# 20190520508.net
KiCad netlist of a schematic drawn in Altium Designer
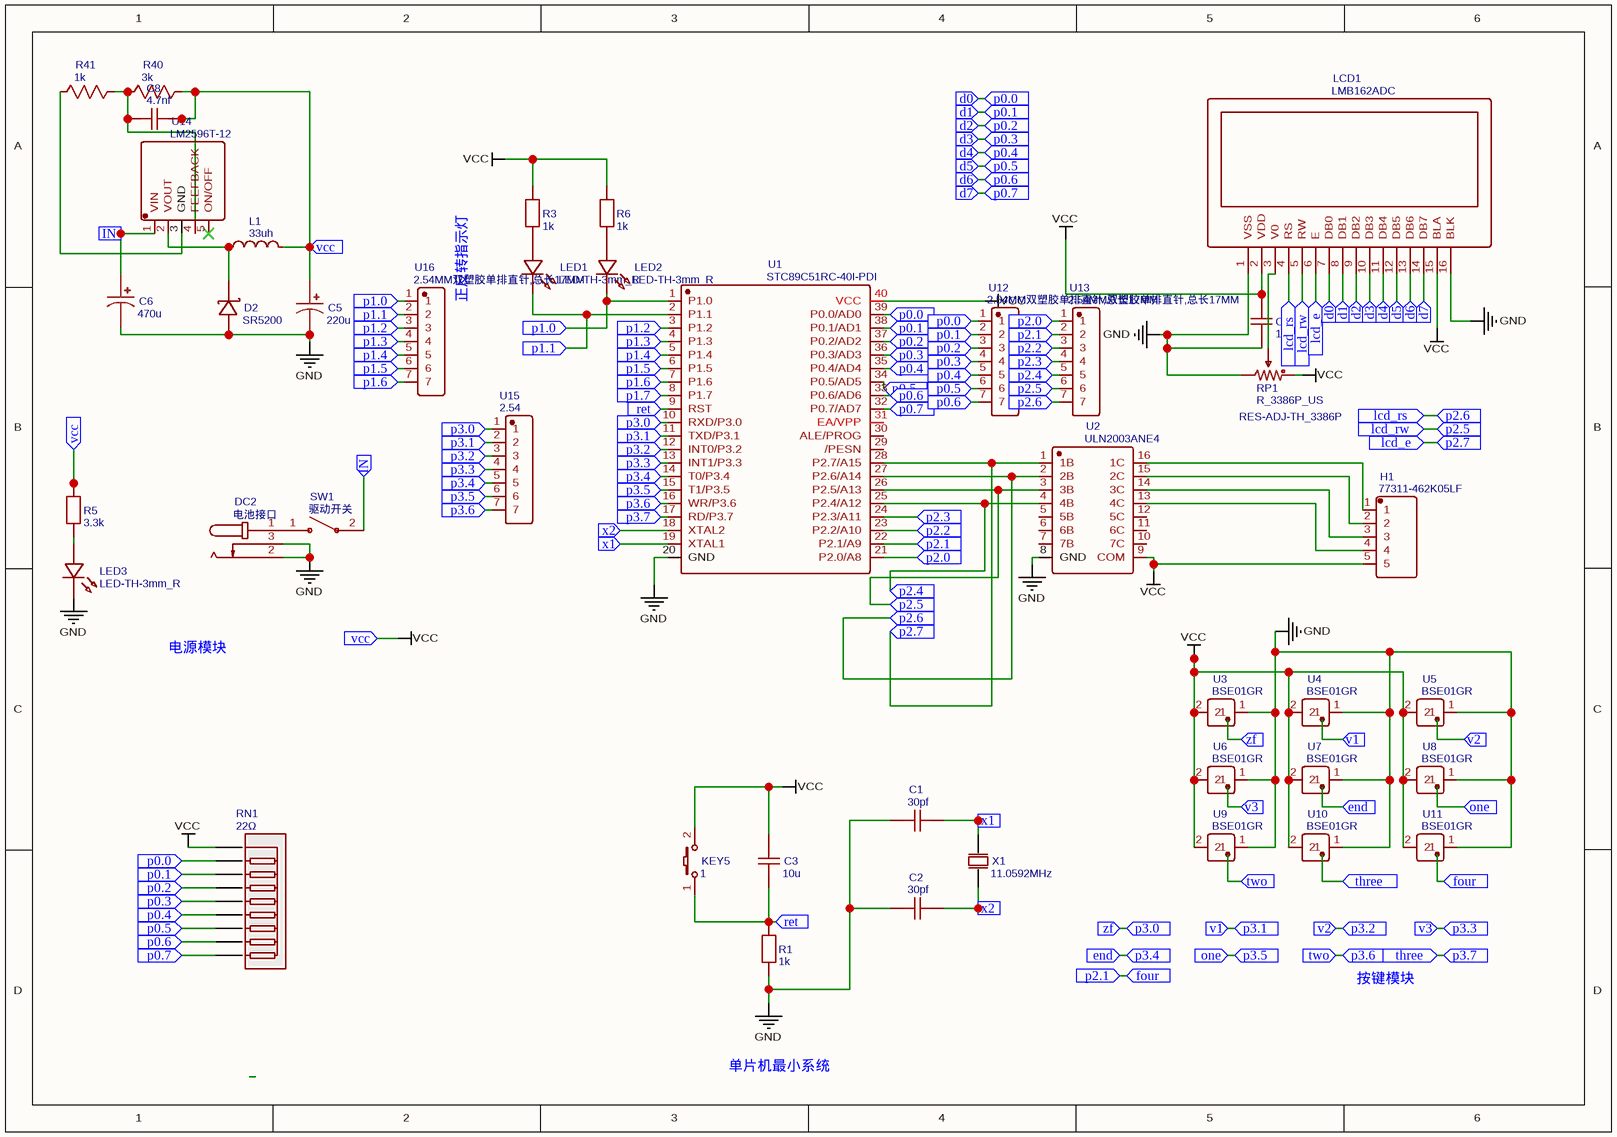
[diagram p0: 20190520508李柯烨电路图.schdoc]

(export (version "E")
  (design (tool "Eeschema 10.0.6"))
  (components
    (comp (ref "C1")
      (value "30pf")
      (fields (field (name "CONTRIBUTOR") "LCEDA_Lib"))
      (libsource (lib "altium-import") (part "root_0_30pf_"))
    )
    (comp (ref "C2")
      (value "30pf")
      (fields (field (name "CONTRIBUTOR") "LCEDA_Lib"))
      (libsource (lib "altium-import") (part "root_0_30pf_"))
    )
    (comp (ref "C3")
      (value "10u")
      (fields (field (name "CONTRIBUTOR") "LCEDA_Lib"))
      (libsource (lib "altium-import") (part "root_1_10u_"))
    )
    (comp (ref "C4")
      (value "104")
      (fields (field (name "CONTRIBUTOR") "LCEDA_Lib"))
      (libsource (lib "altium-import") (part "root_1_104_"))
    )
    (comp (ref "C5")
      (value "220u")
      (fields (field (name "CONTRIBUTOR") "LCEDA_Lib"))
      (libsource (lib "altium-import") (part "root_3_220u_"))
    )
    (comp (ref "C6")
      (value "470u")
      (fields (field (name "CONTRIBUTOR") "LCEDA_Lib"))
      (libsource (lib "altium-import") (part "root_3_470u_"))
    )
    (comp (ref "C8")
      (value "4.7nf")
      (fields (field (name "CONTRIBUTOR") "LCEDA_Lib"))
      (libsource (lib "altium-import") (part "root_0_4.7nf_"))
    )
    (comp (ref "D2")
      (value "SR5200")
      (fields (field (name "BOM_SUPPLIER PART") "C129841") (field (name "CONTRIBUTOR") "LCSC"))
      (libsource (lib "altium-import") (part "root_3_SR5200_"))
    )
    (comp (ref "DC2")
      (value "电池接口")
      (fields
        (field (name "BOM_SUPPLIER PART") "C319138")
        (field (name "BOM_MANUFACTURER PART") "DC-002H-1.3")
        (field (name "CONTRIBUTOR") "LCSC")
      )
      (libsource (lib "altium-import") (part "root_0_电池接口_"))
    )
    (comp (ref "H1")
      (value "77311-462K05LF")
      (fields (field (name "BOM_SUPPLIER PART") "C180219") (field (name "CONTRIBUTOR") "LCSC"))
      (libsource (lib "altium-import") (part "root_0_77311-462K05LF_"))
    )
    (comp (ref "KEY5")
      (value "1")
      (fields
        (field (name "BOM_SUPPLIER PART") "C118141")
        (field (name "BOM_MANUFACTURER PART") "K2-1107ST-A4SW-06")
        (field (name "CONTRIBUTOR") "LCEDA_Lib")
      )
      (libsource (lib "altium-import") (part "root_1_1_"))
    )
    (comp (ref "L1")
      (value "33uh")
      (fields (field (name "CONTRIBUTOR") "LCEDA_Lib"))
      (libsource (lib "altium-import") (part "root_0_33uh_"))
    )
    (comp (ref "LCD1")
      (value "LMB162ADC")
      (fields (field (name "BOM_SUPPLIER PART") "C9741"))
      (libsource (lib "altium-import") (part "root_0_LMB162ADC_"))
    )
    (comp (ref "LED1")
      (value "LED-TH-3mm_R")
      (fields
        (field (name "BOM_MANUFACTURER PART") "204-10SDRD/S530-A3-L")
        (field (name "BOM_SUPPLIER PART") "C84774")
        (field (name "CONTRIBUTOR") "LCEDA_Lib")
      )
      (libsource (lib "altium-import") (part "root_3_LED-TH-3mm_R_"))
    )
    (comp (ref "LED2")
      (value "LED-TH-3mm_R")
      (fields
        (field (name "BOM_MANUFACTURER PART") "204-10SDRD/S530-A3-L")
        (field (name "BOM_SUPPLIER PART") "C84774")
        (field (name "CONTRIBUTOR") "LCEDA_Lib")
      )
      (libsource (lib "altium-import") (part "root_3_LED-TH-3mm_R_"))
    )
    (comp (ref "LED3")
      (value "LED-TH-3mm_R")
      (fields
        (field (name "BOM_MANUFACTURER PART") "204-10SDRD/S530-A3-L")
        (field (name "BOM_SUPPLIER PART") "C84774")
        (field (name "CONTRIBUTOR") "LCEDA_Lib")
      )
      (libsource (lib "altium-import") (part "root_3_LED-TH-3mm_R_"))
    )
    (comp (ref "R1")
      (value "1k")
      (fields (field (name "CONTRIBUTOR") "LCEDA_Lib"))
      (libsource (lib "altium-import") (part "root_1_1k_"))
    )
    (comp (ref "R3")
      (value "1k")
      (fields (field (name "CONTRIBUTOR") "LCEDA_Lib"))
      (libsource (lib "altium-import") (part "root_1_1k_"))
    )
    (comp (ref "R5")
      (value "3.3k")
      (fields (field (name "CONTRIBUTOR") "LCEDA_Lib"))
      (libsource (lib "altium-import") (part "root_3_3.3k_"))
    )
    (comp (ref "R6")
      (value "1k")
      (fields (field (name "CONTRIBUTOR") "LCEDA_Lib"))
      (libsource (lib "altium-import") (part "root_1_1k_"))
    )
    (comp (ref "R40")
      (value "3k")
      (fields (field (name "CONTRIBUTOR") "LCEDA_Lib"))
      (libsource (lib "altium-import") (part "root_0_3k_"))
    )
    (comp (ref "R41")
      (value "1k")
      (fields (field (name "CONTRIBUTOR") "LCEDA_Lib"))
      (libsource (lib "altium-import") (part "root_0_1k_"))
    )
    (comp (ref "RN1")
      (value "22Ω")
      (fields (field (name "BOM_MANUFACTURER PART") "A09-220JP") (field (name "BOM_SUPPLIER PART") "C9105"))
      (libsource (lib "altium-import") (part "root_0_22Ω_"))
    )
    (comp (ref "RP1")
      (value "R_3386P_US")
      (fields (field (name "CONTRIBUTOR") "LCEDA_Lib"))
      (libsource (lib "altium-import") (part "root_0_R_3386P_US_"))
    )
    (comp (ref "SW1")
      (value "驱动开关")
      (fields
        (field (name "BOM_SUPPLIER PART") "C312627")
        (field (name "BOM_MANUFACTURER PART") "RT-S01-145-L1NB1B")
        (field (name "CONTRIBUTOR") "LCSC")
      )
      (libsource (lib "altium-import") (part "root_0_驱动开关_"))
    )
    (comp (ref "U1")
      (value "STC89C51RC-40I-PDI")
      (fields
        (field (name "BOM_MANUFACTURER PART") "STC89C51RC-40I-PDIP40")
        (field (name "BOM_SUPPLIER PART") "C29286")
      )
      (libsource (lib "altium-import") (part "root_0_STC89C51RC-40I-PDI_"))
    )
    (comp (ref "U2") (value "ULN2003ANE4") (libsource (lib "altium-import") (part "root_0_ULN2003ANE4_")))
    (comp (ref "U3")
      (value "BSE01GR")
      (fields (field (name "BOM_SUPPLIER PART") "C3294680") (field (name "CONTRIBUTOR") "lcsc"))
      (libsource (lib "altium-import") (part "root_2_BSE01GR_"))
    )
    (comp (ref "U4")
      (value "BSE01GR")
      (fields (field (name "BOM_SUPPLIER PART") "C3294680") (field (name "CONTRIBUTOR") "lcsc"))
      (libsource (lib "altium-import") (part "root_2_BSE01GR_"))
    )
    (comp (ref "U5")
      (value "BSE01GR")
      (fields (field (name "BOM_SUPPLIER PART") "C3294680") (field (name "CONTRIBUTOR") "lcsc"))
      (libsource (lib "altium-import") (part "root_2_BSE01GR_"))
    )
    (comp (ref "U6")
      (value "BSE01GR")
      (fields (field (name "BOM_SUPPLIER PART") "C3294680") (field (name "CONTRIBUTOR") "lcsc"))
      (libsource (lib "altium-import") (part "root_2_BSE01GR_"))
    )
    (comp (ref "U7")
      (value "BSE01GR")
      (fields (field (name "BOM_SUPPLIER PART") "C3294680") (field (name "CONTRIBUTOR") "lcsc"))
      (libsource (lib "altium-import") (part "root_2_BSE01GR_"))
    )
    (comp (ref "U8")
      (value "BSE01GR")
      (fields (field (name "BOM_SUPPLIER PART") "C3294680") (field (name "CONTRIBUTOR") "lcsc"))
      (libsource (lib "altium-import") (part "root_2_BSE01GR_"))
    )
    (comp (ref "U9")
      (value "BSE01GR")
      (fields (field (name "BOM_SUPPLIER PART") "C3294680") (field (name "CONTRIBUTOR") "lcsc"))
      (libsource (lib "altium-import") (part "root_2_BSE01GR_"))
    )
    (comp (ref "U10")
      (value "BSE01GR")
      (fields (field (name "BOM_SUPPLIER PART") "C3294680") (field (name "CONTRIBUTOR") "lcsc"))
      (libsource (lib "altium-import") (part "root_2_BSE01GR_"))
    )
    (comp (ref "U11")
      (value "BSE01GR")
      (fields (field (name "BOM_SUPPLIER PART") "C3294680") (field (name "CONTRIBUTOR") "lcsc"))
      (libsource (lib "altium-import") (part "root_2_BSE01GR_"))
    )
    (comp (ref "U12")
      (value "2.54MM双塑胶单排直针,总长17MM")
      (fields
        (field (name "BOM_SUPPLIER PART") "C9900001323")
        (field (name "BOM_MANUFACTURER PART") "2.54mm双塑胶单排直针,总长17mm")
        (field (name "CONTRIBUTOR") "LCSC")
      )
      (libsource (lib "altium-import") (part "root_0_2.54MM双塑胶单排直针,总长17MM_"))
    )
    (comp (ref "U13")
      (value "2.54MM双塑胶单排直针,总长17MM")
      (fields
        (field (name "BOM_SUPPLIER PART") "C9900001323")
        (field (name "BOM_MANUFACTURER PART") "2.54mm双塑胶单排直针,总长17mm")
        (field (name "CONTRIBUTOR") "LCSC")
      )
      (libsource (lib "altium-import") (part "root_0_2.54MM双塑胶单排直针,总长17MM_"))
    )
    (comp (ref "U14")
      (value "LM2596T-12")
      (fields (field (name "BOM_SUPPLIER PART") "C126045") (field (name "CONTRIBUTOR") "LCSC"))
      (libsource (lib "altium-import") (part "root_1_LM2596T-12_"))
    )
    (comp (ref "U15")
      (value "2.54")
      (fields
        (field (name "BOM_SUPPLIER PART") "C9900001323")
        (field (name "BOM_MANUFACTURER PART") "2.54mm双塑胶单排直针,总长17mm")
        (field (name "CONTRIBUTOR") "LCSC")
      )
      (libsource (lib "altium-import") (part "root_0_2.54_"))
    )
    (comp (ref "U16")
      (value "2.54MM双塑胶单排直针,总长17MM")
      (fields
        (field (name "BOM_SUPPLIER PART") "C9900001323")
        (field (name "BOM_MANUFACTURER PART") "2.54mm双塑胶单排直针,总长17mm")
        (field (name "CONTRIBUTOR") "LCSC")
      )
      (libsource (lib "altium-import") (part "root_0_2.54MM双塑胶单排直针,总长17MM_"))
    )
    (comp (ref "X1")
      (value "11.0592MHz")
      (fields
        (field (name "BOM_MANUFACTURER PART") "X49UD110592MSD2SC")
        (field (name "BOM_SUPPLIER PART") "C2194")
      )
      (libsource (lib "altium-import") (part "root_1_11.0592MHz_"))
    )
  )
  (nets
    (net (code "1") (name "/IN") (class "Default")
      (node (ref "C6") (pin "1") (pinfunction "1_1") (pintype "passive"))
      (node (ref "SW1") (pin "2") (pinfunction "2_2") (pintype "passive"))
      (node (ref "U14") (pin "1") (pinfunction "VIN_1") (pintype "passive"))
    )
    (net (code "2") (name "/d0") (class "Default")
      (node (ref "LCD1") (pin "7") (pinfunction "DB0_7") (pintype "passive"))
      (node (ref "RN1") (pin "2") (pinfunction "2_2") (pintype "passive"))
      (node (ref "U1") (pin "39") (pinfunction "P0.0/AD0_39") (pintype "passive"))
      (node (ref "U12") (pin "1") (pinfunction "1_1") (pintype "passive"))
    )
    (net (code "3") (name "/d1") (class "Default")
      (node (ref "LCD1") (pin "8") (pinfunction "DB1_8") (pintype "passive"))
      (node (ref "RN1") (pin "3") (pinfunction "3_3") (pintype "passive"))
      (node (ref "U1") (pin "38") (pinfunction "P0.1/AD1_38") (pintype "passive"))
      (node (ref "U12") (pin "2") (pinfunction "2_2") (pintype "passive"))
    )
    (net (code "4") (name "/d2") (class "Default")
      (node (ref "LCD1") (pin "9") (pinfunction "DB2_9") (pintype "passive"))
      (node (ref "RN1") (pin "4") (pinfunction "4_4") (pintype "passive"))
      (node (ref "U1") (pin "37") (pinfunction "P0.2/AD2_37") (pintype "passive"))
      (node (ref "U12") (pin "3") (pinfunction "3_3") (pintype "passive"))
    )
    (net (code "5") (name "/d3") (class "Default")
      (node (ref "LCD1") (pin "10") (pinfunction "DB3_10") (pintype "passive"))
      (node (ref "RN1") (pin "5") (pinfunction "5_5") (pintype "passive"))
      (node (ref "U1") (pin "36") (pinfunction "P0.3/AD3_36") (pintype "passive"))
      (node (ref "U12") (pin "4") (pinfunction "4_4") (pintype "passive"))
    )
    (net (code "6") (name "/d4") (class "Default")
      (node (ref "LCD1") (pin "11") (pinfunction "DB4_11") (pintype "passive"))
      (node (ref "RN1") (pin "6") (pinfunction "6_6") (pintype "passive"))
      (node (ref "U1") (pin "35") (pinfunction "P0.4/AD4_35") (pintype "passive"))
      (node (ref "U12") (pin "5") (pinfunction "5_5") (pintype "passive"))
    )
    (net (code "7") (name "/d5") (class "Default")
      (node (ref "LCD1") (pin "12") (pinfunction "DB5_12") (pintype "passive"))
      (node (ref "RN1") (pin "7") (pinfunction "7_7") (pintype "passive"))
      (node (ref "U1") (pin "34") (pinfunction "P0.5/AD5_34") (pintype "passive"))
      (node (ref "U12") (pin "6") (pinfunction "6_6") (pintype "passive"))
    )
    (net (code "8") (name "/d6") (class "Default")
      (node (ref "LCD1") (pin "13") (pinfunction "DB6_13") (pintype "passive"))
      (node (ref "RN1") (pin "8") (pinfunction "8_8") (pintype "passive"))
      (node (ref "U1") (pin "33") (pinfunction "P0.6/AD6_33") (pintype "passive"))
      (node (ref "U12") (pin "7") (pinfunction "7_7") (pintype "passive"))
    )
    (net (code "9") (name "/d7") (class "Default")
      (node (ref "LCD1") (pin "14") (pinfunction "DB7_14") (pintype "passive"))
      (node (ref "RN1") (pin "9") (pinfunction "9_9") (pintype "passive"))
      (node (ref "U1") (pin "32") (pinfunction "P0.7/AD7_32") (pintype "passive"))
    )
    (net (code "10") (name "/end") (class "Default")
      (node (ref "U1") (pin "14") (pinfunction "T0/P3.4_14") (pintype "passive"))
      (node (ref "U15") (pin "5") (pinfunction "5_5") (pintype "passive"))
    )
    (net (code "11") (name "/four") (class "Default")
      (node (ref "U1") (pin "22") (pinfunction "P2.1/A9_22") (pintype "passive"))
      (node (ref "U13") (pin "2") (pinfunction "2_2") (pintype "passive"))
    )
    (net (code "12") (name "/lcd_e") (class "Default")
      (node (ref "LCD1") (pin "6") (pinfunction "E_6") (pintype "passive"))
      (node (ref "U1") (pin "28") (pinfunction "P2.7/A15_28") (pintype "passive"))
      (node (ref "U2") (pin "1") (pinfunction "1B_1") (pintype "passive"))
    )
    (net (code "13") (name "/lcd_rs") (class "Default")
      (node (ref "LCD1") (pin "4") (pinfunction "RS_4") (pintype "passive"))
      (node (ref "U1") (pin "27") (pinfunction "P2.6/A14_27") (pintype "passive"))
      (node (ref "U13") (pin "7") (pinfunction "7_7") (pintype "passive"))
      (node (ref "U2") (pin "2") (pinfunction "2B_2") (pintype "passive"))
    )
    (net (code "14") (name "/lcd_rw") (class "Default")
      (node (ref "LCD1") (pin "5") (pinfunction "RW_5") (pintype "passive"))
      (node (ref "U1") (pin "26") (pinfunction "P2.5/A13_26") (pintype "passive"))
      (node (ref "U13") (pin "6") (pinfunction "6_6") (pintype "passive"))
      (node (ref "U2") (pin "3") (pinfunction "3B_3") (pintype "passive"))
    )
    (net (code "15") (name "/one") (class "Default")
      (node (ref "U1") (pin "15") (pinfunction "T1/P3.5_15") (pintype "passive"))
      (node (ref "U15") (pin "6") (pinfunction "6_6") (pintype "passive"))
    )
    (net (code "16") (name "/p1.0") (class "Default")
      (node (ref "LED2") (pin "2") (pinfunction "2_2") (pintype "passive"))
      (node (ref "U1") (pin "1") (pinfunction "P1.0_1") (pintype "passive"))
      (node (ref "U16") (pin "1") (pinfunction "1_1") (pintype "passive"))
    )
    (net (code "17") (name "/p1.1") (class "Default")
      (node (ref "LED1") (pin "2") (pinfunction "2_2") (pintype "passive"))
      (node (ref "U1") (pin "2") (pinfunction "P1.1_2") (pintype "passive"))
      (node (ref "U16") (pin "2") (pinfunction "2_2") (pintype "passive"))
    )
    (net (code "18") (name "/p1.2") (class "Default")
      (node (ref "U1") (pin "3") (pinfunction "P1.2_3") (pintype "passive"))
      (node (ref "U16") (pin "3") (pinfunction "3_3") (pintype "passive"))
    )
    (net (code "19") (name "/p1.3") (class "Default")
      (node (ref "U1") (pin "4") (pinfunction "P1.3_4") (pintype "passive"))
      (node (ref "U16") (pin "4") (pinfunction "4_4") (pintype "passive"))
    )
    (net (code "20") (name "/p1.4") (class "Default")
      (node (ref "U1") (pin "5") (pinfunction "P1.4_5") (pintype "passive"))
      (node (ref "U16") (pin "5") (pinfunction "5_5") (pintype "passive"))
    )
    (net (code "21") (name "/p1.5") (class "Default")
      (node (ref "U1") (pin "6") (pinfunction "P1.5_6") (pintype "passive"))
      (node (ref "U16") (pin "6") (pinfunction "6_6") (pintype "passive"))
    )
    (net (code "22") (name "/p1.6") (class "Default")
      (node (ref "U1") (pin "7") (pinfunction "P1.6_7") (pintype "passive"))
      (node (ref "U16") (pin "7") (pinfunction "7_7") (pintype "passive"))
    )
    (net (code "23") (name "/p1.7") (class "Default")
      (node (ref "U1") (pin "8") (pinfunction "P1.7_8") (pintype "passive"))
    )
    (net (code "24") (name "/p2.0") (class "Default")
      (node (ref "U1") (pin "21") (pinfunction "P2.0/A8_21") (pintype "passive"))
      (node (ref "U13") (pin "1") (pinfunction "1_1") (pintype "passive"))
    )
    (net (code "25") (name "/p2.2") (class "Default")
      (node (ref "U1") (pin "23") (pinfunction "P2.2/A10_23") (pintype "passive"))
      (node (ref "U13") (pin "3") (pinfunction "3_3") (pintype "passive"))
    )
    (net (code "26") (name "/p2.3") (class "Default")
      (node (ref "U1") (pin "24") (pinfunction "P2.3/A11_24") (pintype "passive"))
      (node (ref "U13") (pin "4") (pinfunction "4_4") (pintype "passive"))
    )
    (net (code "27") (name "/p2.4") (class "Default")
      (node (ref "U1") (pin "25") (pinfunction "P2.4/A12_25") (pintype "passive"))
      (node (ref "U13") (pin "5") (pinfunction "5_5") (pintype "passive"))
      (node (ref "U2") (pin "4") (pinfunction "4B_4") (pintype "passive"))
    )
    (net (code "28") (name "/p3.0") (class "Default")
      (node (ref "U1") (pin "10") (pinfunction "RXD/P3.0_10") (pintype "passive"))
      (node (ref "U15") (pin "1") (pinfunction "1_1") (pintype "passive"))
    )
    (net (code "29") (name "/p3.1") (class "Default")
      (node (ref "U1") (pin "11") (pinfunction "TXD/P3.1_11") (pintype "passive"))
      (node (ref "U15") (pin "2") (pinfunction "2_2") (pintype "passive"))
    )
    (net (code "30") (name "/p3.2") (class "Default")
      (node (ref "U1") (pin "12") (pinfunction "INT0/P3.2_12") (pintype "passive"))
      (node (ref "U15") (pin "3") (pinfunction "3_3") (pintype "passive"))
    )
    (net (code "31") (name "/p3.3") (class "Default")
      (node (ref "U1") (pin "13") (pinfunction "INT1/P3.3_13") (pintype "passive"))
      (node (ref "U15") (pin "4") (pinfunction "4_4") (pintype "passive"))
    )
    (net (code "32") (name "/p3.6") (class "Default")
      (node (ref "U1") (pin "16") (pinfunction "WR/P3.6_16") (pintype "passive"))
      (node (ref "U15") (pin "7") (pinfunction "7_7") (pintype "passive"))
    )
    (net (code "33") (name "/p3.7") (class "Default")
      (node (ref "U1") (pin "17") (pinfunction "RD/P3.7_17") (pintype "passive"))
    )
    (net (code "34") (name "/ret") (class "Default")
      (node (ref "C3") (pin "1") (pinfunction "1_1") (pintype "passive"))
      (node (ref "KEY5") (pin "1") (pinfunction "1_1") (pintype "passive"))
      (node (ref "R1") (pin "2") (pinfunction "2_2") (pintype "passive"))
      (node (ref "U1") (pin "9") (pinfunction "RST_9") (pintype "passive"))
    )
    (net (code "35") (name "/x1") (class "Default")
      (node (ref "C1") (pin "2") (pinfunction "2_2") (pintype "passive"))
      (node (ref "U1") (pin "19") (pinfunction "XTAL1_19") (pintype "passive"))
      (node (ref "X1") (pin "1") (pinfunction "OSC1_1") (pintype "passive"))
    )
    (net (code "36") (name "/x2") (class "Default")
      (node (ref "C2") (pin "2") (pinfunction "2_2") (pintype "passive"))
      (node (ref "U1") (pin "18") (pinfunction "XTAL2_18") (pintype "passive"))
      (node (ref "X1") (pin "2") (pinfunction "OSC2_2") (pintype "passive"))
    )
    (net (code "37") (name "GND") (class "Default")
      (node (ref "C1") (pin "1") (pinfunction "1_1") (pintype "passive"))
      (node (ref "C2") (pin "1") (pinfunction "1_1") (pintype "passive"))
      (node (ref "C4") (pin "1") (pinfunction "1_1") (pintype "passive"))
      (node (ref "C5") (pin "2") (pinfunction "2_2") (pintype "passive"))
      (node (ref "C6") (pin "2") (pinfunction "2_2") (pintype "passive"))
      (node (ref "D2") (pin "2") (pinfunction "A_2") (pintype "passive"))
      (node (ref "DC2") (pin "2") (pinfunction "2_2") (pintype "passive"))
      (node (ref "DC2") (pin "3") (pinfunction "3_3") (pintype "passive"))
      (node (ref "LCD1") (pin "1") (pinfunction "VSS_1") (pintype "passive"))
      (node (ref "LCD1") (pin "16") (pinfunction "BLK_16") (pintype "passive"))
      (node (ref "LED3") (pin "2") (pinfunction "2_2") (pintype "passive"))
      (node (ref "R1") (pin "1") (pinfunction "1_1") (pintype "passive"))
      (node (ref "RP1") (pin "3") (pinfunction "3_3") (pintype "passive"))
      (node (ref "U1") (pin "20") (pinfunction "GND_20") (pintype "passive"))
      (node (ref "U10") (pin "1") (pinfunction "1_1") (pintype "passive"))
      (node (ref "U11") (pin "1") (pinfunction "1_1") (pintype "passive"))
      (node (ref "U2") (pin "8") (pinfunction "GND_8") (pintype "passive"))
      (node (ref "U3") (pin "1") (pinfunction "1_1") (pintype "passive"))
      (node (ref "U4") (pin "1") (pinfunction "1_1") (pintype "passive"))
      (node (ref "U5") (pin "1") (pinfunction "1_1") (pintype "passive"))
      (node (ref "U6") (pin "1") (pinfunction "1_1") (pintype "passive"))
      (node (ref "U7") (pin "1") (pinfunction "1_1") (pintype "passive"))
      (node (ref "U8") (pin "1") (pinfunction "1_1") (pintype "passive"))
      (node (ref "U9") (pin "1") (pinfunction "1_1") (pintype "passive"))
    )
    (net (code "38") (name "Net-(D2-C)") (class "Default")
      (node (ref "D2") (pin "1") (pinfunction "C_1") (pintype "passive"))
      (node (ref "L1") (pin "1") (pinfunction "1_1") (pintype "passive"))
      (node (ref "U14") (pin "2") (pinfunction "VOUT_2") (pintype "passive"))
    )
    (net (code "39") (name "Net-(DC2-Pad1)") (class "Default")
      (node (ref "DC2") (pin "1") (pinfunction "1_1") (pintype "passive"))
      (node (ref "SW1") (pin "1") (pinfunction "1_1") (pintype "passive"))
    )
    (net (code "40") (name "Net-(LCD1-V0)") (class "Default")
      (node (ref "LCD1") (pin "3") (pinfunction "V0_3") (pintype "passive"))
      (node (ref "RP1") (pin "2") (pinfunction "2_2") (pintype "passive"))
    )
    (net (code "41") (name "Net-(LED1-Pad1)") (class "Default")
      (node (ref "LED1") (pin "1") (pinfunction "1_1") (pintype "passive"))
      (node (ref "R3") (pin "1") (pinfunction "1_1") (pintype "passive"))
    )
    (net (code "42") (name "Net-(LED2-Pad1)") (class "Default")
      (node (ref "LED2") (pin "1") (pinfunction "1_1") (pintype "passive"))
      (node (ref "R6") (pin "1") (pinfunction "1_1") (pintype "passive"))
    )
    (net (code "43") (name "Net-(LED3-Pad1)") (class "Default")
      (node (ref "LED3") (pin "1") (pinfunction "1_1") (pintype "passive"))
      (node (ref "R5") (pin "2") (pinfunction "2_2") (pintype "passive"))
    )
    (net (code "44") (name "Net-(U2-1C)") (class "Default")
      (node (ref "H1") (pin "1") (pinfunction "1_1") (pintype "passive"))
      (node (ref "U2") (pin "16") (pinfunction "1C_16") (pintype "passive"))
    )
    (net (code "45") (name "Net-(U2-2C)") (class "Default")
      (node (ref "H1") (pin "2") (pinfunction "2_2") (pintype "passive"))
      (node (ref "U2") (pin "15") (pinfunction "2C_15") (pintype "passive"))
    )
    (net (code "46") (name "Net-(U2-3C)") (class "Default")
      (node (ref "H1") (pin "3") (pinfunction "3_3") (pintype "passive"))
      (node (ref "U2") (pin "14") (pinfunction "3C_14") (pintype "passive"))
    )
    (net (code "47") (name "Net-(U2-4C)") (class "Default")
      (node (ref "H1") (pin "4") (pinfunction "4_4") (pintype "passive"))
      (node (ref "U2") (pin "13") (pinfunction "4C_13") (pintype "passive"))
    )
    (net (code "48") (name "Net-(U14-FEEFBACK)") (class "Default")
      (node (ref "C8") (pin "1") (pinfunction "1_1") (pintype "passive"))
      (node (ref "R40") (pin "1") (pinfunction "1_1") (pintype "passive"))
      (node (ref "R41") (pin "2") (pinfunction "2_2") (pintype "passive"))
      (node (ref "U14") (pin "4") (pinfunction "FEEFBACK_4") (pintype "passive"))
    )
    (net (code "49") (name "Net-(U14-GND)") (class "Default")
      (node (ref "R41") (pin "1") (pinfunction "1_1") (pintype "passive"))
      (node (ref "U14") (pin "3") (pinfunction "GND_3") (pintype "passive"))
    )
    (net (code "50") (name "VCC") (class "Default")
      (node (ref "C3") (pin "2") (pinfunction "2_2") (pintype "passive"))
      (node (ref "C4") (pin "2") (pinfunction "2_2") (pintype "passive"))
      (node (ref "C5") (pin "1") (pinfunction "1_1") (pintype "passive"))
      (node (ref "C8") (pin "2") (pinfunction "2_2") (pintype "passive"))
      (node (ref "H1") (pin "5") (pinfunction "5_5") (pintype "passive"))
      (node (ref "KEY5") (pin "2") (pinfunction "2_2") (pintype "passive"))
      (node (ref "L1") (pin "2") (pinfunction "2_2") (pintype "passive"))
      (node (ref "LCD1") (pin "15") (pinfunction "BLA_15") (pintype "passive"))
      (node (ref "LCD1") (pin "2") (pinfunction "VDD_2") (pintype "passive"))
      (node (ref "R3") (pin "2") (pinfunction "2_2") (pintype "passive"))
      (node (ref "R40") (pin "2") (pinfunction "2_2") (pintype "passive"))
      (node (ref "R5") (pin "1") (pinfunction "1_1") (pintype "passive"))
      (node (ref "R6") (pin "2") (pinfunction "2_2") (pintype "passive"))
      (node (ref "RN1") (pin "1") (pinfunction "1_1") (pintype "passive"))
      (node (ref "RP1") (pin "1") (pinfunction "1_1") (pintype "passive"))
      (node (ref "U1") (pin "40") (pinfunction "VCC_40") (pintype "passive"))
      (node (ref "U10") (pin "2") (pinfunction "2_2") (pintype "passive"))
      (node (ref "U11") (pin "2") (pinfunction "2_2") (pintype "passive"))
      (node (ref "U2") (pin "9") (pinfunction "COM_9") (pintype "passive"))
      (node (ref "U3") (pin "2") (pinfunction "2_2") (pintype "passive"))
      (node (ref "U4") (pin "2") (pinfunction "2_2") (pintype "passive"))
      (node (ref "U5") (pin "2") (pinfunction "2_2") (pintype "passive"))
      (node (ref "U6") (pin "2") (pinfunction "2_2") (pintype "passive"))
      (node (ref "U7") (pin "2") (pinfunction "2_2") (pintype "passive"))
      (node (ref "U8") (pin "2") (pinfunction "2_2") (pintype "passive"))
      (node (ref "U9") (pin "2") (pinfunction "2_2") (pintype "passive"))
    )
    (net (code "51") (name "unconnected-(U1-ALE{slash}PROG-Pad30)") (class "Default")
      (node (ref "U1") (pin "30") (pinfunction "ALE/PROG_30") (pintype "passive"))
    )
    (net (code "52") (name "unconnected-(U1-EA{slash}VPP-Pad31)") (class "Default")
      (node (ref "U1") (pin "31") (pinfunction "EA/VPP_31") (pintype "passive"))
    )
    (net (code "53") (name "unconnected-(U1-{slash}PESN-Pad29)") (class "Default")
      (node (ref "U1") (pin "29") (pinfunction "/PESN_29") (pintype "passive"))
    )
    (net (code "54") (name "unconnected-(U2-5B-Pad5)") (class "Default")
      (node (ref "U2") (pin "5") (pinfunction "5B_5") (pintype "passive"))
    )
    (net (code "55") (name "unconnected-(U2-5C-Pad12)") (class "Default")
      (node (ref "U2") (pin "12") (pinfunction "5C_12") (pintype "passive"))
    )
    (net (code "56") (name "unconnected-(U2-6B-Pad6)") (class "Default")
      (node (ref "U2") (pin "6") (pinfunction "6B_6") (pintype "passive"))
    )
    (net (code "57") (name "unconnected-(U2-6C-Pad11)") (class "Default")
      (node (ref "U2") (pin "11") (pinfunction "6C_11") (pintype "passive"))
    )
    (net (code "58") (name "unconnected-(U2-7B-Pad7)") (class "Default")
      (node (ref "U2") (pin "7") (pinfunction "7B_7") (pintype "passive"))
    )
    (net (code "59") (name "unconnected-(U2-7C-Pad10)") (class "Default")
      (node (ref "U2") (pin "10") (pinfunction "7C_10") (pintype "passive"))
    )
    (net (code "60") (name "unconnected-(U14-ON{slash}OFF-Pad5)") (class "Default")
      (node (ref "U14") (pin "5") (pinfunction "ON/OFF_5") (pintype "passive+no_connect"))
    )
  )
)
